# ATX_Buttons_Board.net
KiCad netlist of a schematic drawn in EAGLE
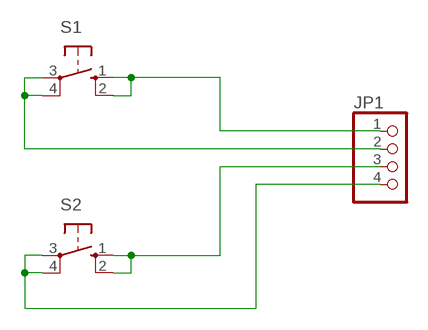
[diagram p0: schematic, sheet 1]

(export (version "E")
  (design (tool "Eeschema 10.0.6"))
  (components
    (comp (ref "JP1")
      (value "PINHD-1X4/90")
      (footprint "eagle-import:1X04_90")
      (libsource (lib "eagle-import") (part "PINHD-1X4/90"))
    )
    (comp (ref "S1")
      (value "10-XX")
      (footprint "eagle-import:B3F-10XX")
      (fields (field (name "MPN") "B3F-1000"))
      (libsource (lib "eagle-import") (part "10-XX"))
    )
    (comp (ref "S2")
      (value "10-XX")
      (footprint "eagle-import:B3F-10XX")
      (fields (field (name "MPN") "B3F-1000"))
      (libsource (lib "eagle-import") (part "10-XX"))
    )
  )
  (nets
    (net (code "1") (name "Net-(S1-P)") (class "Default")
      (node (ref "JP1") (pin "2") (pinfunction "2_2") (pintype "passive"))
      (node (ref "S1") (pin "3") (pinfunction "P_3") (pintype "passive"))
      (node (ref "S1") (pin "4") (pinfunction "P1_4") (pintype "passive"))
    )
    (net (code "2") (name "Net-(S1-S)") (class "Default")
      (node (ref "JP1") (pin "1") (pinfunction "1_1") (pintype "passive"))
      (node (ref "S1") (pin "1") (pinfunction "S_1") (pintype "passive"))
      (node (ref "S1") (pin "2") (pinfunction "S1_2") (pintype "passive"))
    )
    (net (code "3") (name "Net-(S2-P)") (class "Default")
      (node (ref "JP1") (pin "4") (pinfunction "4_4") (pintype "passive"))
      (node (ref "S2") (pin "3") (pinfunction "P_3") (pintype "passive"))
      (node (ref "S2") (pin "4") (pinfunction "P1_4") (pintype "passive"))
    )
    (net (code "4") (name "Net-(S2-S)") (class "Default")
      (node (ref "JP1") (pin "3") (pinfunction "3_3") (pintype "passive"))
      (node (ref "S2") (pin "1") (pinfunction "S_1") (pintype "passive"))
      (node (ref "S2") (pin "2") (pinfunction "S1_2") (pintype "passive"))
    )
  )
)
